# HedleySensorRevD2.net
KiCad netlist of a schematic drawn in EAGLE
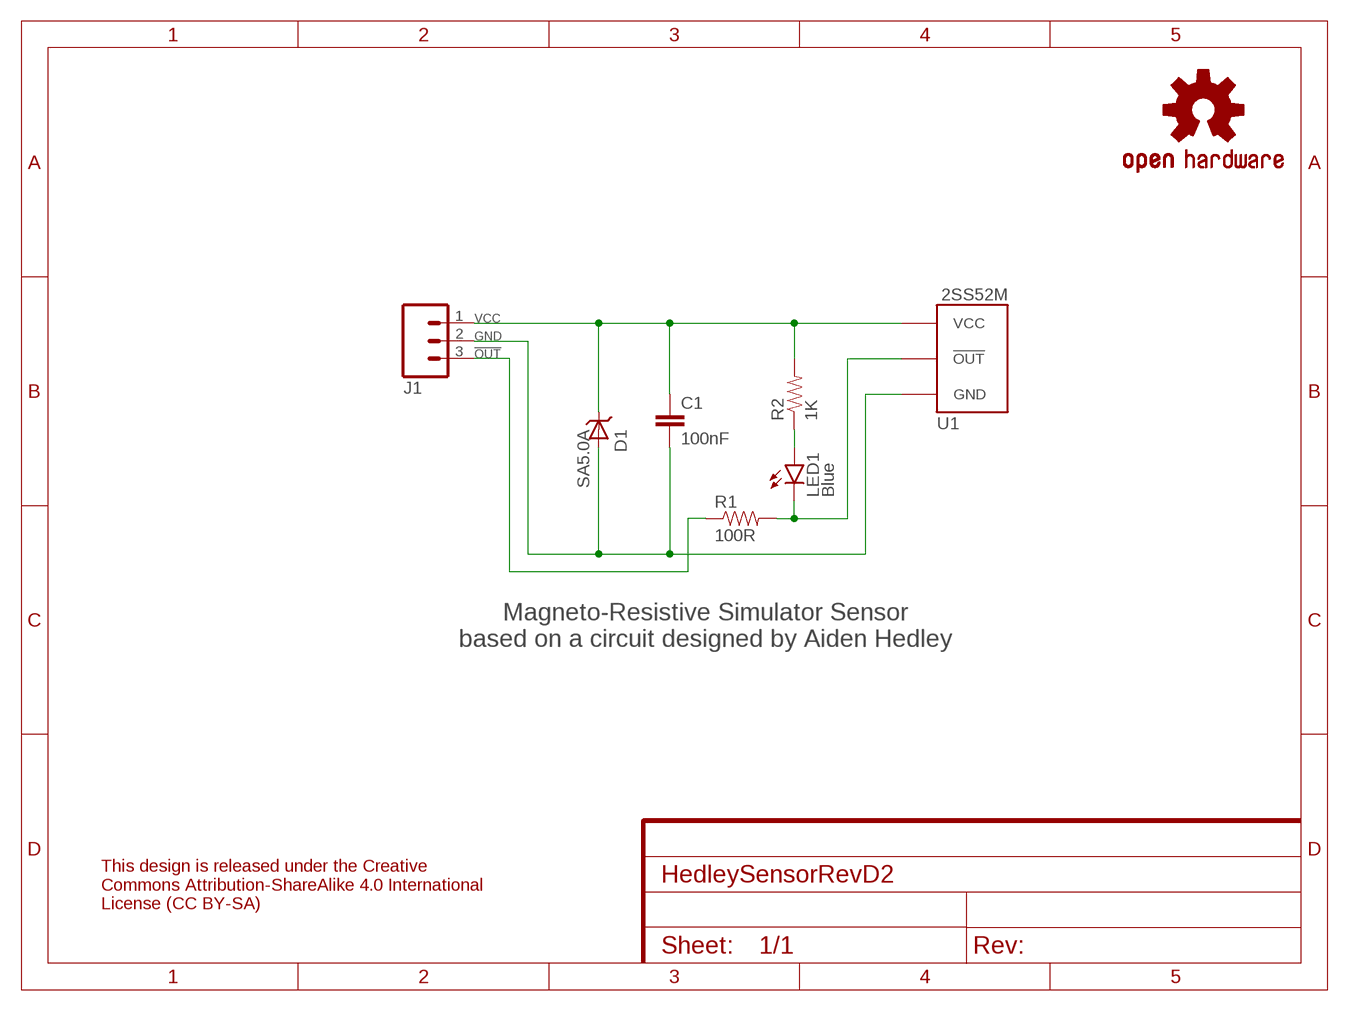
[diagram p0: schematic, sheet 1]

(export (version "E")
  (design (tool "Eeschema 10.0.6"))
  (components
    (comp (ref "C1")
      (value "100nF")
      (footprint "eagle-import:CAP-PTH-SMALL")
      (libsource (lib "eagle-import") (part "CAPPTH"))
    )
    (comp (ref "D1")
      (value "SA5.0A")
      (footprint "eagle-import:DO41_TVS_UNI")
      (libsource (lib "eagle-import") (part "SA5.0A"))
    )
    (comp (ref "J1")
      (value "M03PTH")
      (footprint "eagle-import:1X03")
      (libsource (lib "eagle-import") (part "M03PTH"))
    )
    (comp (ref "LED1")
      (value "Blue")
      (footprint "eagle-import:LED3MM")
      (libsource (lib "eagle-import") (part "LED3MM"))
    )
    (comp (ref "LOGO1")
      (value "OSHW-LOGOS")
      (footprint "eagle-import:OSHW-LOGO-S")
      (libsource (lib "eagle-import") (part "OSHW-LOGOS"))
    )
    (comp (ref "R1")
      (value "100R")
      (footprint "eagle-import:AXIAL-0.4")
      (libsource (lib "eagle-import") (part "RESISTORPTH-1/4W"))
    )
    (comp (ref "R2")
      (value "1K")
      (footprint "eagle-import:AXIAL-0.4")
      (libsource (lib "eagle-import") (part "RESISTORPTH-1/4W"))
    )
    (comp (ref "U1")
      (value "2SS52MFLAT")
      (footprint "eagle-import:2SS52M_FLAT")
      (libsource (lib "eagle-import") (part "2SS52MFLAT"))
    )
  )
  (nets
    (net (code "1") (name "/GND") (class "Default")
      (node (ref "C1") (pin "2") (pinfunction "2_2") (pintype "passive"))
      (node (ref "D1") (pin "ANODE") (pinfunction "ANODE_ANODE") (pintype "passive"))
      (node (ref "J1") (pin "2") (pinfunction "2_2") (pintype "passive"))
      (node (ref "U1") (pin "P$1") (pinfunction "GND_P$1") (pintype "bidirectional"))
    )
    (net (code "2") (name "/VCC") (class "Default")
      (node (ref "C1") (pin "1") (pinfunction "1_1") (pintype "passive"))
      (node (ref "D1") (pin "CATHODE") (pinfunction "CATHODE_CATHODE") (pintype "passive"))
      (node (ref "J1") (pin "1") (pinfunction "1_1") (pintype "passive"))
      (node (ref "R2") (pin "P$2") (pinfunction "2_P$2") (pintype "passive"))
      (node (ref "U1") (pin "P$3") (pinfunction "VCC_P$3") (pintype "bidirectional"))
    )
    (net (code "3") (name "/~{OUT}") (class "Default")
      (node (ref "J1") (pin "3") (pinfunction "3_3") (pintype "passive"))
      (node (ref "R1") (pin "P$1") (pinfunction "1_P$1") (pintype "passive"))
    )
    (net (code "4") (name "Net-(LED1-C)") (class "Default")
      (node (ref "LED1") (pin "K") (pinfunction "C_K") (pintype "passive"))
      (node (ref "R1") (pin "P$2") (pinfunction "2_P$2") (pintype "passive"))
      (node (ref "U1") (pin "P$2") (pinfunction "~{OUT}_P$2") (pintype "bidirectional"))
    )
    (net (code "5") (name "Net-(R2-1)") (class "Default")
      (node (ref "LED1") (pin "A") (pinfunction "A_A") (pintype "passive"))
      (node (ref "R2") (pin "P$1") (pinfunction "1_P$1") (pintype "passive"))
    )
  )
)
